# LPF_1_0.net
KiCad netlist of a schematic drawn in EAGLE
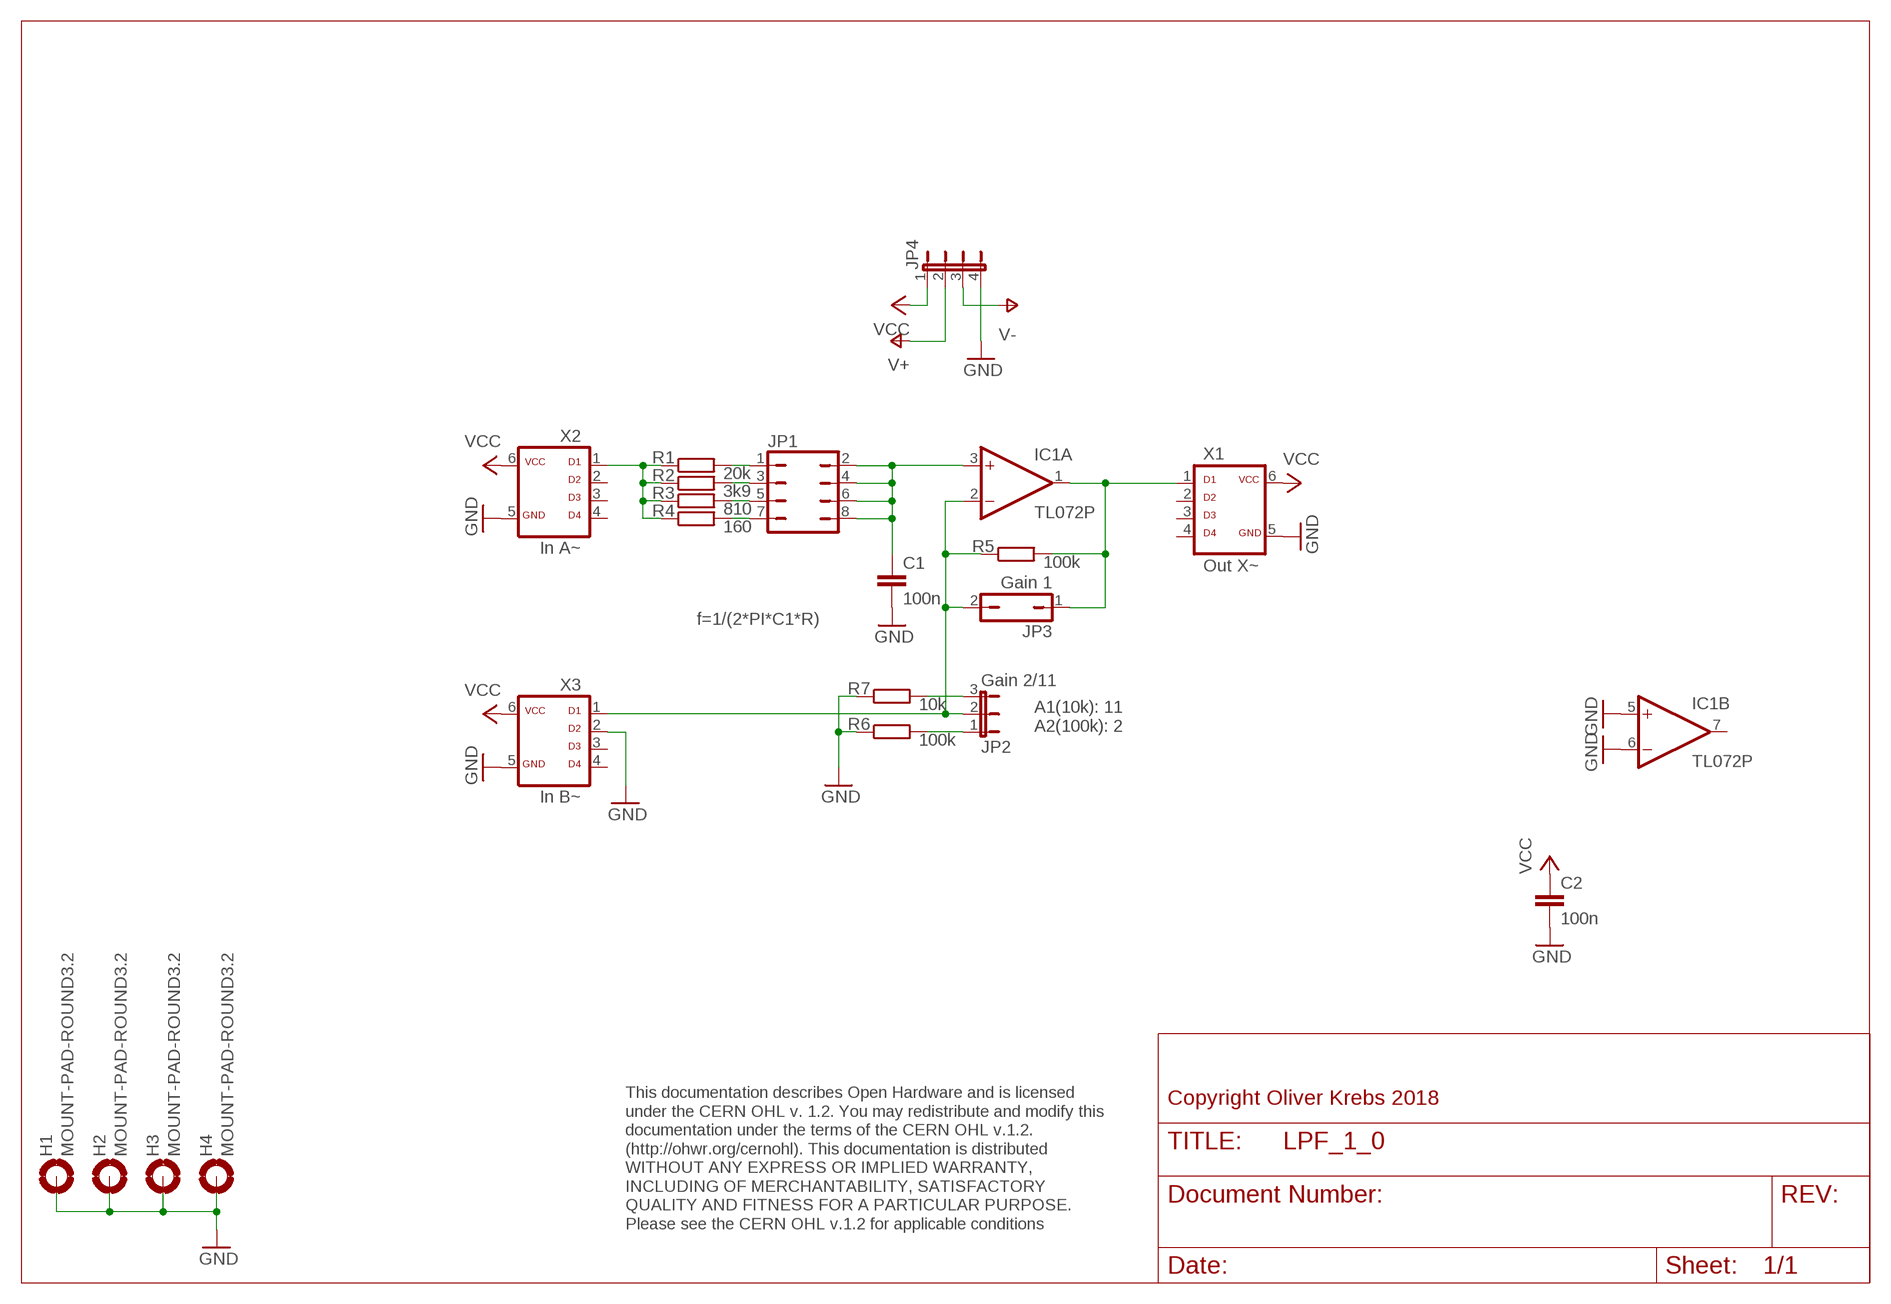
[diagram p0: schematic, sheet 1]

(export (version "E")
  (design (tool "Eeschema 10.0.6"))
  (components
    (comp (ref "C1")
      (value "100n")
      (footprint "eagle-import:C050-025X075")
      (libsource (lib "eagle-import") (part "C-EU050-025X075"))
    )
    (comp (ref "C2")
      (value "100n")
      (footprint "eagle-import:C050-025X075")
      (libsource (lib "eagle-import") (part "C-EU050-025X075"))
    )
    (comp (ref "H1")
      (value "MOUNT-PAD-ROUND3.2")
      (footprint "eagle-import:3,2-PAD")
      (libsource (lib "eagle-import") (part "MOUNT-PAD-ROUND3.2"))
    )
    (comp (ref "H2")
      (value "MOUNT-PAD-ROUND3.2")
      (footprint "eagle-import:3,2-PAD")
      (libsource (lib "eagle-import") (part "MOUNT-PAD-ROUND3.2"))
    )
    (comp (ref "H3")
      (value "MOUNT-PAD-ROUND3.2")
      (footprint "eagle-import:3,2-PAD")
      (libsource (lib "eagle-import") (part "MOUNT-PAD-ROUND3.2"))
    )
    (comp (ref "H4")
      (value "MOUNT-PAD-ROUND3.2")
      (footprint "eagle-import:3,2-PAD")
      (libsource (lib "eagle-import") (part "MOUNT-PAD-ROUND3.2"))
    )
    (comp (ref "IC1")
      (value "TL072P")
      (footprint "eagle-import:DIL08")
      (libsource (lib "eagle-import") (part "TL072P"))
    )
    (comp (ref "JP1")
      (value "JP4Q")
      (footprint "eagle-import:JP4Q")
      (libsource (lib "eagle-import") (part "JP4Q"))
    )
    (comp (ref "JP2")
      (value "Gain 2/11")
      (footprint "eagle-import:JP2-U")
      (libsource (lib "eagle-import") (part "JP2EJP2-U"))
    )
    (comp (ref "JP3")
      (value "Gain 1")
      (footprint "eagle-import:JP1")
      (libsource (lib "eagle-import") (part "JP1Q"))
    )
    (comp (ref "JP4")
      (value "JP4E")
      (footprint "eagle-import:JP4")
      (libsource (lib "eagle-import") (part "JP4E"))
    )
    (comp (ref "R1")
      (value "20k")
      (footprint "eagle-import:0207_10")
      (libsource (lib "eagle-import") (part "R-EU_0207/10"))
    )
    (comp (ref "R2")
      (value "3k9")
      (footprint "eagle-import:0207_10")
      (libsource (lib "eagle-import") (part "R-EU_0207/10"))
    )
    (comp (ref "R3")
      (value "810")
      (footprint "eagle-import:0207_10")
      (libsource (lib "eagle-import") (part "R-EU_0207/10"))
    )
    (comp (ref "R4")
      (value "160")
      (footprint "eagle-import:0207_10")
      (libsource (lib "eagle-import") (part "R-EU_0207/10"))
    )
    (comp (ref "R5")
      (value "100k")
      (footprint "eagle-import:0207_10")
      (libsource (lib "eagle-import") (part "R-EU_0207/10"))
    )
    (comp (ref "R6")
      (value "100k")
      (footprint "eagle-import:0207_10")
      (libsource (lib "eagle-import") (part "R-EU_0207/10"))
    )
    (comp (ref "R7")
      (value "10k")
      (footprint "eagle-import:0207_10")
      (libsource (lib "eagle-import") (part "R-EU_0207/10"))
    )
    (comp (ref "X1")
      (value "Out X~")
      (footprint "eagle-import:ML-6")
      (libsource (lib "eagle-import") (part "ML6D"))
    )
    (comp (ref "X2")
      (value "In A~")
      (footprint "eagle-import:ML-6")
      (libsource (lib "eagle-import") (part "ML6D"))
    )
    (comp (ref "X3")
      (value "In B~")
      (footprint "eagle-import:ML-6")
      (libsource (lib "eagle-import") (part "ML6D"))
    )
  )
  (nets
    (net (code "1") (name "GND") (class "Default")
      (node (ref "C1") (pin "2") (pinfunction "2_2") (pintype "passive"))
      (node (ref "C2") (pin "2") (pinfunction "2_2") (pintype "passive"))
      (node (ref "H1") (pin "B3,2") (pinfunction "MOUNT_B3,2") (pintype "passive"))
      (node (ref "H2") (pin "B3,2") (pinfunction "MOUNT_B3,2") (pintype "passive"))
      (node (ref "H3") (pin "B3,2") (pinfunction "MOUNT_B3,2") (pintype "passive"))
      (node (ref "H4") (pin "B3,2") (pinfunction "MOUNT_B3,2") (pintype "passive"))
      (node (ref "IC1") (pin "5") (pinfunction "+IN_5") (pintype "input"))
      (node (ref "IC1") (pin "6") (pinfunction "-IN_6") (pintype "input"))
      (node (ref "JP4") (pin "4") (pinfunction "4_4") (pintype "passive"))
      (node (ref "R6") (pin "1") (pinfunction "1_1") (pintype "passive"))
      (node (ref "R7") (pin "1") (pinfunction "1_1") (pintype "passive"))
      (node (ref "X1") (pin "5") (pinfunction "5_5") (pintype "passive"))
      (node (ref "X2") (pin "5") (pinfunction "5_5") (pintype "passive"))
      (node (ref "X3") (pin "2") (pinfunction "2_2") (pintype "passive"))
      (node (ref "X3") (pin "5") (pinfunction "5_5") (pintype "passive"))
    )
    (net (code "2") (name "Net-(IC1A-+IN)") (class "Default")
      (node (ref "C1") (pin "1") (pinfunction "1_1") (pintype "passive"))
      (node (ref "IC1") (pin "3") (pinfunction "+IN_3") (pintype "input"))
      (node (ref "JP1") (pin "2") (pinfunction "2_2") (pintype "passive"))
      (node (ref "JP1") (pin "4") (pinfunction "4_4") (pintype "passive"))
      (node (ref "JP1") (pin "6") (pinfunction "6_6") (pintype "passive"))
      (node (ref "JP1") (pin "8") (pinfunction "8_8") (pintype "passive"))
    )
    (net (code "3") (name "Net-(IC1A--IN)") (class "Default")
      (node (ref "IC1") (pin "2") (pinfunction "-IN_2") (pintype "input"))
      (node (ref "JP2") (pin "2") (pinfunction "2_2") (pintype "passive"))
      (node (ref "JP3") (pin "2") (pinfunction "2_2") (pintype "passive"))
      (node (ref "R5") (pin "1") (pinfunction "1_1") (pintype "passive"))
      (node (ref "X3") (pin "1") (pinfunction "1_1") (pintype "passive"))
    )
    (net (code "4") (name "Net-(IC1A-OUT)") (class "Default")
      (node (ref "IC1") (pin "1") (pinfunction "OUT_1") (pintype "output"))
      (node (ref "JP3") (pin "1") (pinfunction "1_1") (pintype "passive"))
      (node (ref "R5") (pin "2") (pinfunction "2_2") (pintype "passive"))
      (node (ref "X1") (pin "1") (pinfunction "1_1") (pintype "passive"))
    )
    (net (code "5") (name "Net-(JP1-Pad1)") (class "Default")
      (node (ref "JP1") (pin "1") (pinfunction "1_1") (pintype "passive"))
      (node (ref "R1") (pin "2") (pinfunction "2_2") (pintype "passive"))
    )
    (net (code "6") (name "Net-(JP1-Pad3)") (class "Default")
      (node (ref "JP1") (pin "3") (pinfunction "3_3") (pintype "passive"))
      (node (ref "R2") (pin "2") (pinfunction "2_2") (pintype "passive"))
    )
    (net (code "7") (name "Net-(JP1-Pad5)") (class "Default")
      (node (ref "JP1") (pin "5") (pinfunction "5_5") (pintype "passive"))
      (node (ref "R3") (pin "2") (pinfunction "2_2") (pintype "passive"))
    )
    (net (code "8") (name "Net-(JP1-Pad7)") (class "Default")
      (node (ref "JP1") (pin "7") (pinfunction "7_7") (pintype "passive"))
      (node (ref "R4") (pin "2") (pinfunction "2_2") (pintype "passive"))
    )
    (net (code "9") (name "Net-(JP2-Pad1)") (class "Default")
      (node (ref "JP2") (pin "1") (pinfunction "1_1") (pintype "passive"))
      (node (ref "R6") (pin "2") (pinfunction "2_2") (pintype "passive"))
    )
    (net (code "10") (name "Net-(JP2-Pad3)") (class "Default")
      (node (ref "JP2") (pin "3") (pinfunction "3_3") (pintype "passive"))
      (node (ref "R7") (pin "2") (pinfunction "2_2") (pintype "passive"))
    )
    (net (code "11") (name "Net-(R1-Pad1)") (class "Default")
      (node (ref "R1") (pin "1") (pinfunction "1_1") (pintype "passive"))
      (node (ref "R2") (pin "1") (pinfunction "1_1") (pintype "passive"))
      (node (ref "R3") (pin "1") (pinfunction "1_1") (pintype "passive"))
      (node (ref "R4") (pin "1") (pinfunction "1_1") (pintype "passive"))
      (node (ref "X2") (pin "1") (pinfunction "1_1") (pintype "passive"))
    )
    (net (code "12") (name "V+") (class "Default")
      (node (ref "JP4") (pin "2") (pinfunction "2_2") (pintype "passive"))
    )
    (net (code "13") (name "V-") (class "Default")
      (node (ref "JP4") (pin "3") (pinfunction "3_3") (pintype "passive"))
    )
    (net (code "14") (name "VCC") (class "Default")
      (node (ref "C2") (pin "1") (pinfunction "1_1") (pintype "passive"))
      (node (ref "JP4") (pin "1") (pinfunction "1_1") (pintype "passive"))
      (node (ref "X1") (pin "6") (pinfunction "6_6") (pintype "passive"))
      (node (ref "X2") (pin "6") (pinfunction "6_6") (pintype "passive"))
      (node (ref "X3") (pin "6") (pinfunction "6_6") (pintype "passive"))
    )
    (net (code "15") (name "unconnected-(IC1B-OUT-Pad7)") (class "Default")
      (node (ref "IC1") (pin "7") (pinfunction "OUT_7") (pintype "output"))
    )
    (net (code "16") (name "unconnected-(X1-Pad2)") (class "Default")
      (node (ref "X1") (pin "2") (pinfunction "2_2") (pintype "passive"))
    )
    (net (code "17") (name "unconnected-(X1-Pad3)") (class "Default")
      (node (ref "X1") (pin "3") (pinfunction "3_3") (pintype "passive"))
    )
    (net (code "18") (name "unconnected-(X1-Pad4)") (class "Default")
      (node (ref "X1") (pin "4") (pinfunction "4_4") (pintype "passive"))
    )
    (net (code "19") (name "unconnected-(X2-Pad2)") (class "Default")
      (node (ref "X2") (pin "2") (pinfunction "2_2") (pintype "passive"))
    )
    (net (code "20") (name "unconnected-(X2-Pad3)") (class "Default")
      (node (ref "X2") (pin "3") (pinfunction "3_3") (pintype "passive"))
    )
    (net (code "21") (name "unconnected-(X2-Pad4)") (class "Default")
      (node (ref "X2") (pin "4") (pinfunction "4_4") (pintype "passive"))
    )
    (net (code "22") (name "unconnected-(X3-Pad3)") (class "Default")
      (node (ref "X3") (pin "3") (pinfunction "3_3") (pintype "passive"))
    )
    (net (code "23") (name "unconnected-(X3-Pad4)") (class "Default")
      (node (ref "X3") (pin "4") (pinfunction "4_4") (pintype "passive"))
    )
  )
)
